# TI_DS26C31T.net
KiCad netlist of a schematic drawn in Altium Designer
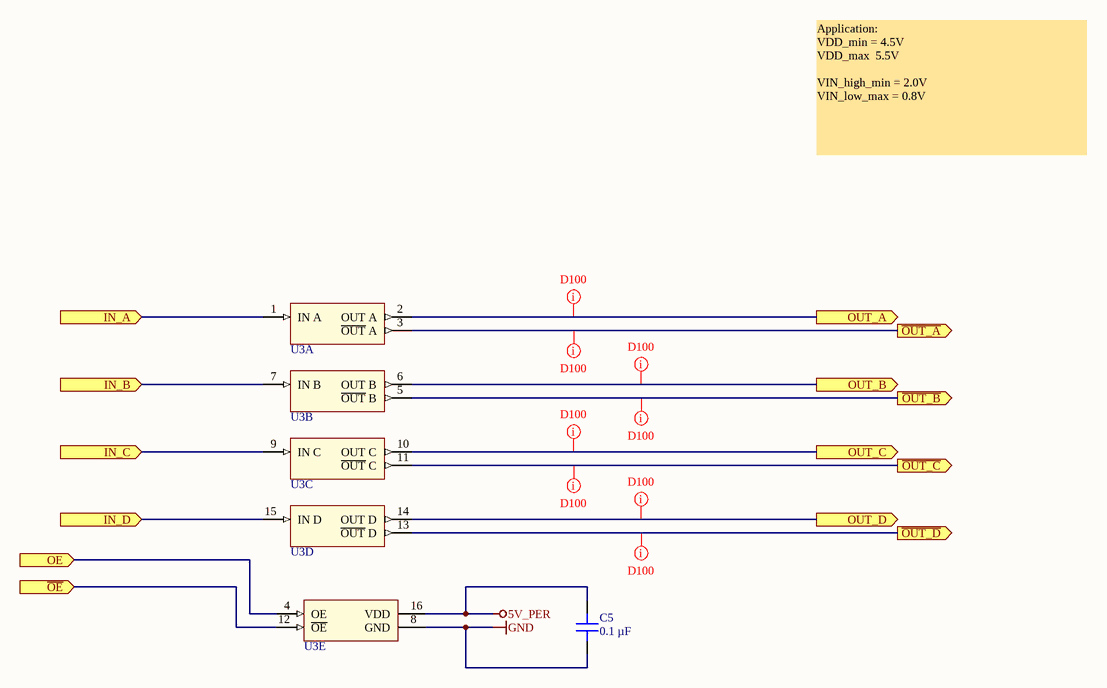
[diagram p0: TI_DS26C31T.SchDoc]

(export (version "E")
  (design (tool "Eeschema 10.0.6"))
  (components
    (comp (ref "C5")
      (value "0.1 µF")
      (footprint "C_0603")
      (description "Capacitor 0603, 50 VDC, 0.1 µF, X7R")
      (fields
        (field (name "MANUFACTURER PART NUMBER") "C0603X104K5RAC7411")
        (field (name "MANUFACTURER") "KEMET")
        (field (name "CREATED FROM") "MGremer")
      )
      (libsource (lib "user") (part "Capacitor"))
    )
    (comp (ref "U3")
      (value "DS26C31TMX/NOPB")
      (footprint "TI_D-R-PDSO-G16_N")
      (description "CMOS Quad Tri-State Differential Line Drivers, 16-pin Narrow SOIC, Pb-Free")
      (fields
        (field (name "MANUFACTURER") "Texas Instruments")
        (field (name "LCSC PART NUMBER") "C132085")
        (field (name "CREATED FROM") "T. Wendt")
      )
      (libsource (lib "user") (part "DS26C31TMX"))
    )
  )
  (nets
    (net (code "1") (name "/IN_A") (class "Default")
      (node (ref "U3") (pin "1") (pinfunction "IN_A_1") (pintype "input"))
    )
    (net (code "2") (name "/IN_B") (class "Default")
      (node (ref "U3") (pin "7") (pinfunction "IN_B_7") (pintype "input"))
    )
    (net (code "3") (name "/IN_C") (class "Default")
      (node (ref "U3") (pin "9") (pinfunction "IN_C_9") (pintype "input"))
    )
    (net (code "4") (name "/IN_D") (class "Default")
      (node (ref "U3") (pin "15") (pinfunction "IN_D_15") (pintype "input"))
    )
    (net (code "5") (name "/OE") (class "Default")
      (node (ref "U3") (pin "4") (pinfunction "OE_4") (pintype "input"))
    )
    (net (code "6") (name "/OUT_A") (class "Default")
      (node (ref "U3") (pin "2") (pinfunction "OUT_A_2") (pintype "output"))
    )
    (net (code "7") (name "/OUT_B") (class "Default")
      (node (ref "U3") (pin "6") (pinfunction "OUT_B_6") (pintype "output"))
    )
    (net (code "8") (name "/OUT_C") (class "Default")
      (node (ref "U3") (pin "10") (pinfunction "OUT_C_10") (pintype "output"))
    )
    (net (code "9") (name "/OUT_D") (class "Default")
      (node (ref "U3") (pin "14") (pinfunction "OUT_D_14") (pintype "output"))
    )
    (net (code "10") (name "/~{OE}") (class "Default")
      (node (ref "U3") (pin "12") (pinfunction "~{OE}_12") (pintype "input"))
    )
    (net (code "11") (name "/~{OUT_A}") (class "Default")
      (node (ref "U3") (pin "3") (pinfunction "~{OUT}_A_3") (pintype "output"))
    )
    (net (code "12") (name "/~{OUT_B}") (class "Default")
      (node (ref "U3") (pin "5") (pinfunction "~{OUT}_B_5") (pintype "output"))
    )
    (net (code "13") (name "/~{OUT_C}") (class "Default")
      (node (ref "U3") (pin "11") (pinfunction "~{OUT}_C_11") (pintype "output"))
    )
    (net (code "14") (name "/~{OUT_D}") (class "Default")
      (node (ref "U3") (pin "13") (pinfunction "~{OUT}_D_13") (pintype "output"))
    )
    (net (code "15") (name "5V_PER") (class "Default")
      (node (ref "C5") (pin "2") (pinfunction "2_2") (pintype "passive"))
      (node (ref "U3") (pin "16") (pinfunction "VDD_16") (pintype "power_in"))
    )
    (net (code "16") (name "GND") (class "Default")
      (node (ref "C5") (pin "1") (pinfunction "1_1") (pintype "passive"))
      (node (ref "U3") (pin "8") (pinfunction "GND_8") (pintype "power_in"))
    )
  )
)
